# Grove_-Mini_Camera_v1_0.net
KiCad netlist of a schematic drawn in EAGLE
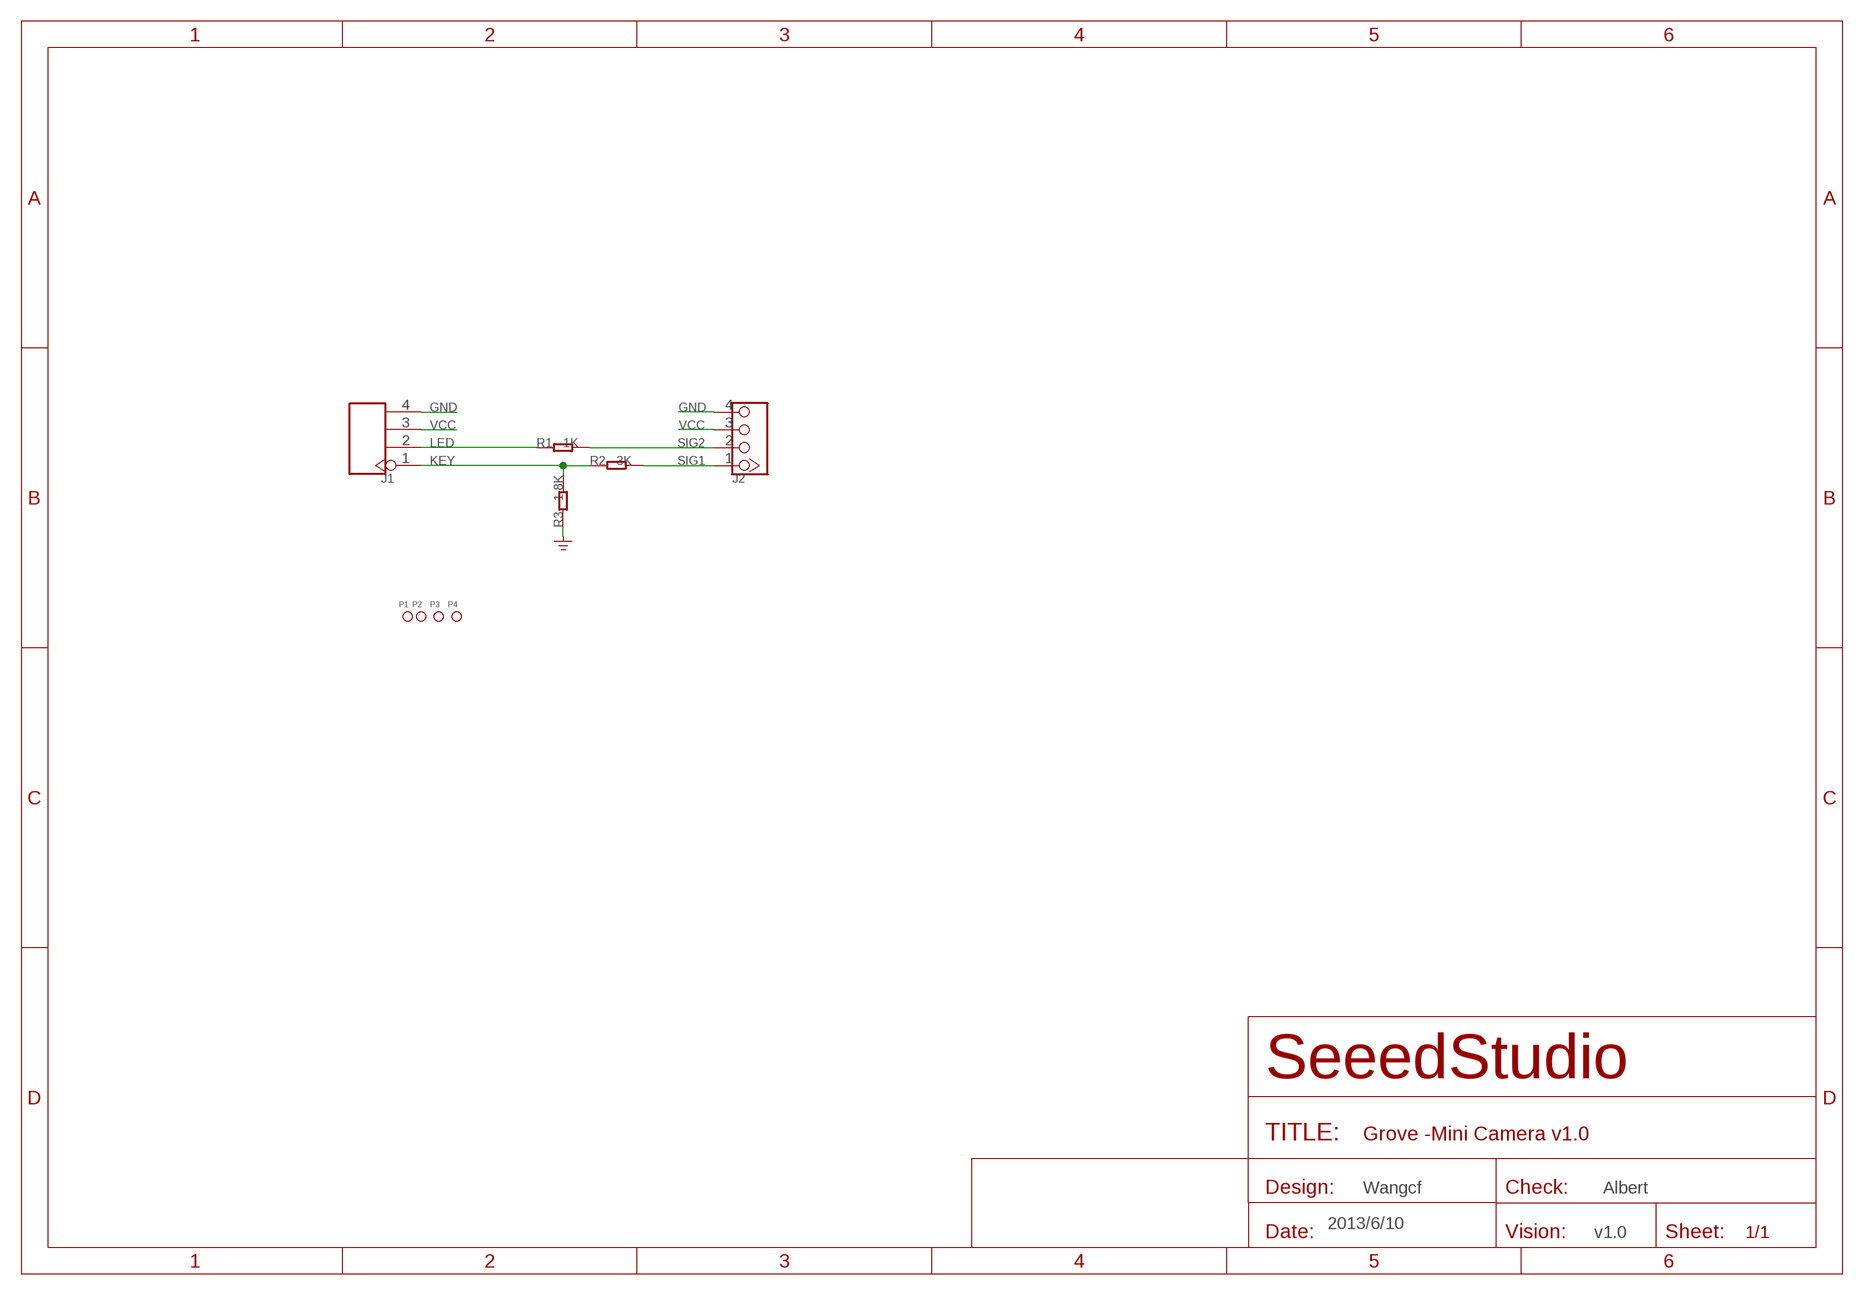
[diagram p0: schematic, sheet 1]

(export (version "E")
  (design (tool "Eeschema 10.0.6"))
  (components
    (comp (ref "J1")
      (value "HEADER-4P-65/35MIL")
      (footprint "eagle-import:4P-65_35MIL")
      (libsource (lib "eagle-import") (part "HEADER-4P-65/35MIL"))
    )
    (comp (ref "J2")
      (value "TWIG-4P-2.0'90D'")
      (footprint "eagle-import:4P-2.0-90D")
      (libsource (lib "eagle-import") (part "TWIG-4P-2.0'90D'"))
    )
    (comp (ref "P1")
      (value "PAD-MARK")
      (footprint "eagle-import:ROUND-MARK-1.0")
      (fields (field (name "PARTNO") "DNP"))
      (libsource (lib "eagle-import") (part "PAD-MARK"))
    )
    (comp (ref "P2")
      (value "PAD-MARK")
      (footprint "eagle-import:ROUND-MARK-1.0")
      (fields (field (name "PARTNO") "DNP"))
      (libsource (lib "eagle-import") (part "PAD-MARK"))
    )
    (comp (ref "P3")
      (value "PAD-MARK")
      (footprint "eagle-import:ROUND-MARK-1.0")
      (fields (field (name "PARTNO") "DNP"))
      (libsource (lib "eagle-import") (part "PAD-MARK"))
    )
    (comp (ref "P4")
      (value "PAD-MARK")
      (footprint "eagle-import:ROUND-MARK-1.0")
      (fields (field (name "PARTNO") "DNP"))
      (libsource (lib "eagle-import") (part "PAD-MARK"))
    )
    (comp (ref "R1")
      (value "1K")
      (footprint "eagle-import:R0603")
      (libsource (lib "eagle-import") (part "R-0603"))
    )
    (comp (ref "R2")
      (value "3K")
      (footprint "eagle-import:R0603")
      (libsource (lib "eagle-import") (part "R-0603"))
    )
    (comp (ref "R3")
      (value "1.8K")
      (footprint "eagle-import:R0603")
      (libsource (lib "eagle-import") (part "R-0603"))
    )
  )
  (nets
    (net (code "1") (name "/KEY") (class "Default")
      (node (ref "J1") (pin "1") (pinfunction "P$1_1") (pintype "bidirectional"))
      (node (ref "R2") (pin "1") (pinfunction "1_1") (pintype "passive"))
      (node (ref "R3") (pin "2") (pinfunction "2_2") (pintype "passive"))
    )
    (net (code "2") (name "/LED") (class "Default")
      (node (ref "J1") (pin "2") (pinfunction "P$2_2") (pintype "bidirectional"))
      (node (ref "R1") (pin "1") (pinfunction "1_1") (pintype "passive"))
    )
    (net (code "3") (name "/SIG1") (class "Default")
      (node (ref "J2") (pin "1") (pinfunction "1_1") (pintype "bidirectional"))
      (node (ref "R2") (pin "2") (pinfunction "2_2") (pintype "passive"))
    )
    (net (code "4") (name "/SIG2") (class "Default")
      (node (ref "J2") (pin "2") (pinfunction "2_2") (pintype "bidirectional"))
      (node (ref "R1") (pin "2") (pinfunction "2_2") (pintype "passive"))
    )
    (net (code "5") (name "/VCC") (class "Default")
      (node (ref "J1") (pin "3") (pinfunction "P$3_3") (pintype "bidirectional"))
      (node (ref "J2") (pin "3") (pinfunction "3_3") (pintype "bidirectional"))
    )
    (net (code "6") (name "GND_POWER") (class "Default")
      (node (ref "J1") (pin "4") (pinfunction "P$4_4") (pintype "bidirectional"))
      (node (ref "J2") (pin "4") (pinfunction "4_4") (pintype "bidirectional"))
      (node (ref "R3") (pin "1") (pinfunction "1_1") (pintype "passive"))
    )
  )
)
